# BUZZERS.net
KiCad netlist of a schematic drawn in Altium Designer
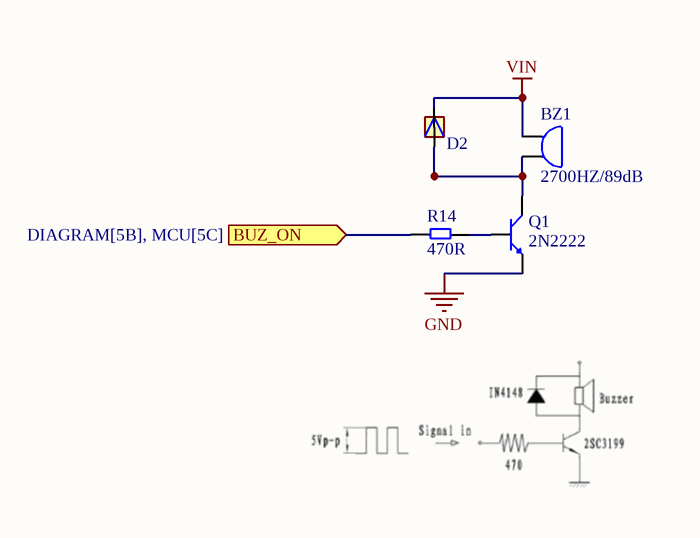
[diagram p0: BUZZERS.SchDoc]

(export (version "E")
  (design (tool "Eeschema 10.0.6"))
  (components
    (comp (ref "BZ1") (value "2700HZ/89dB") (footprint "BUZZER_1209") (libsource (lib "ID") (part "BUZZER")))
    (comp (ref "D2")
      (value "0.15A/75V")
      (footprint "SOD323")
      (description "1N4148W Diode Chỉnh Lưu 0.15A 75V SOD323")
      (fields (field (name "MF") "Diotec Semiconductor") (field (name "MP") "1N4148WS"))
      (libsource (lib "Database_Libs1") (part "DIODE"))
    )
    (comp (ref "Q1")
      (value "2N2222")
      (footprint "TO92254P470H750-3")
      (description "P2N2222A Transistor NPN 40V 0.6A 3 Chân TO-92")
      (libsource (lib "Database_Libs1") (part "BJT_NPN"))
    )
    (comp (ref "R14")
      (value "470R")
      (footprint "RES-SMD-0805")
      (description "Điện Trở 470 Ohm 0805 1%")
      (libsource (lib "Database_Libs1") (part "RES_SMD"))
    )
  )
  (nets
    (net (code "1") (name "/BUZ_ON") (class "Default")
      (node (ref "R14") (pin "1") (pinfunction "1_1") (pintype "passive"))
    )
    (net (code "2") (name "GND") (class "Default")
      (node (ref "Q1") (pin "1") (pinfunction "E_1") (pintype "passive"))
    )
    (net (code "3") (name "Net-(Q1-B)") (class "Default")
      (node (ref "Q1") (pin "3") (pinfunction "B_3") (pintype "passive"))
      (node (ref "R14") (pin "2") (pinfunction "2_2") (pintype "passive"))
    )
    (net (code "4") (name "Net-(Q1-C)") (class "Default")
      (node (ref "BZ1") (pin "2") (pinfunction "2_2") (pintype "passive"))
      (node (ref "D2") (pin "A") (pinfunction "A_A") (pintype "passive"))
      (node (ref "Q1") (pin "2") (pinfunction "C_2") (pintype "passive"))
    )
    (net (code "5") (name "VIN") (class "Default")
      (node (ref "BZ1") (pin "1") (pinfunction "1_1") (pintype "passive"))
      (node (ref "D2") (pin "C") (pinfunction "C_C") (pintype "passive"))
    )
  )
)
